# 3_F2838_GPIO.net
KiCad netlist of a schematic drawn in Altium Designer
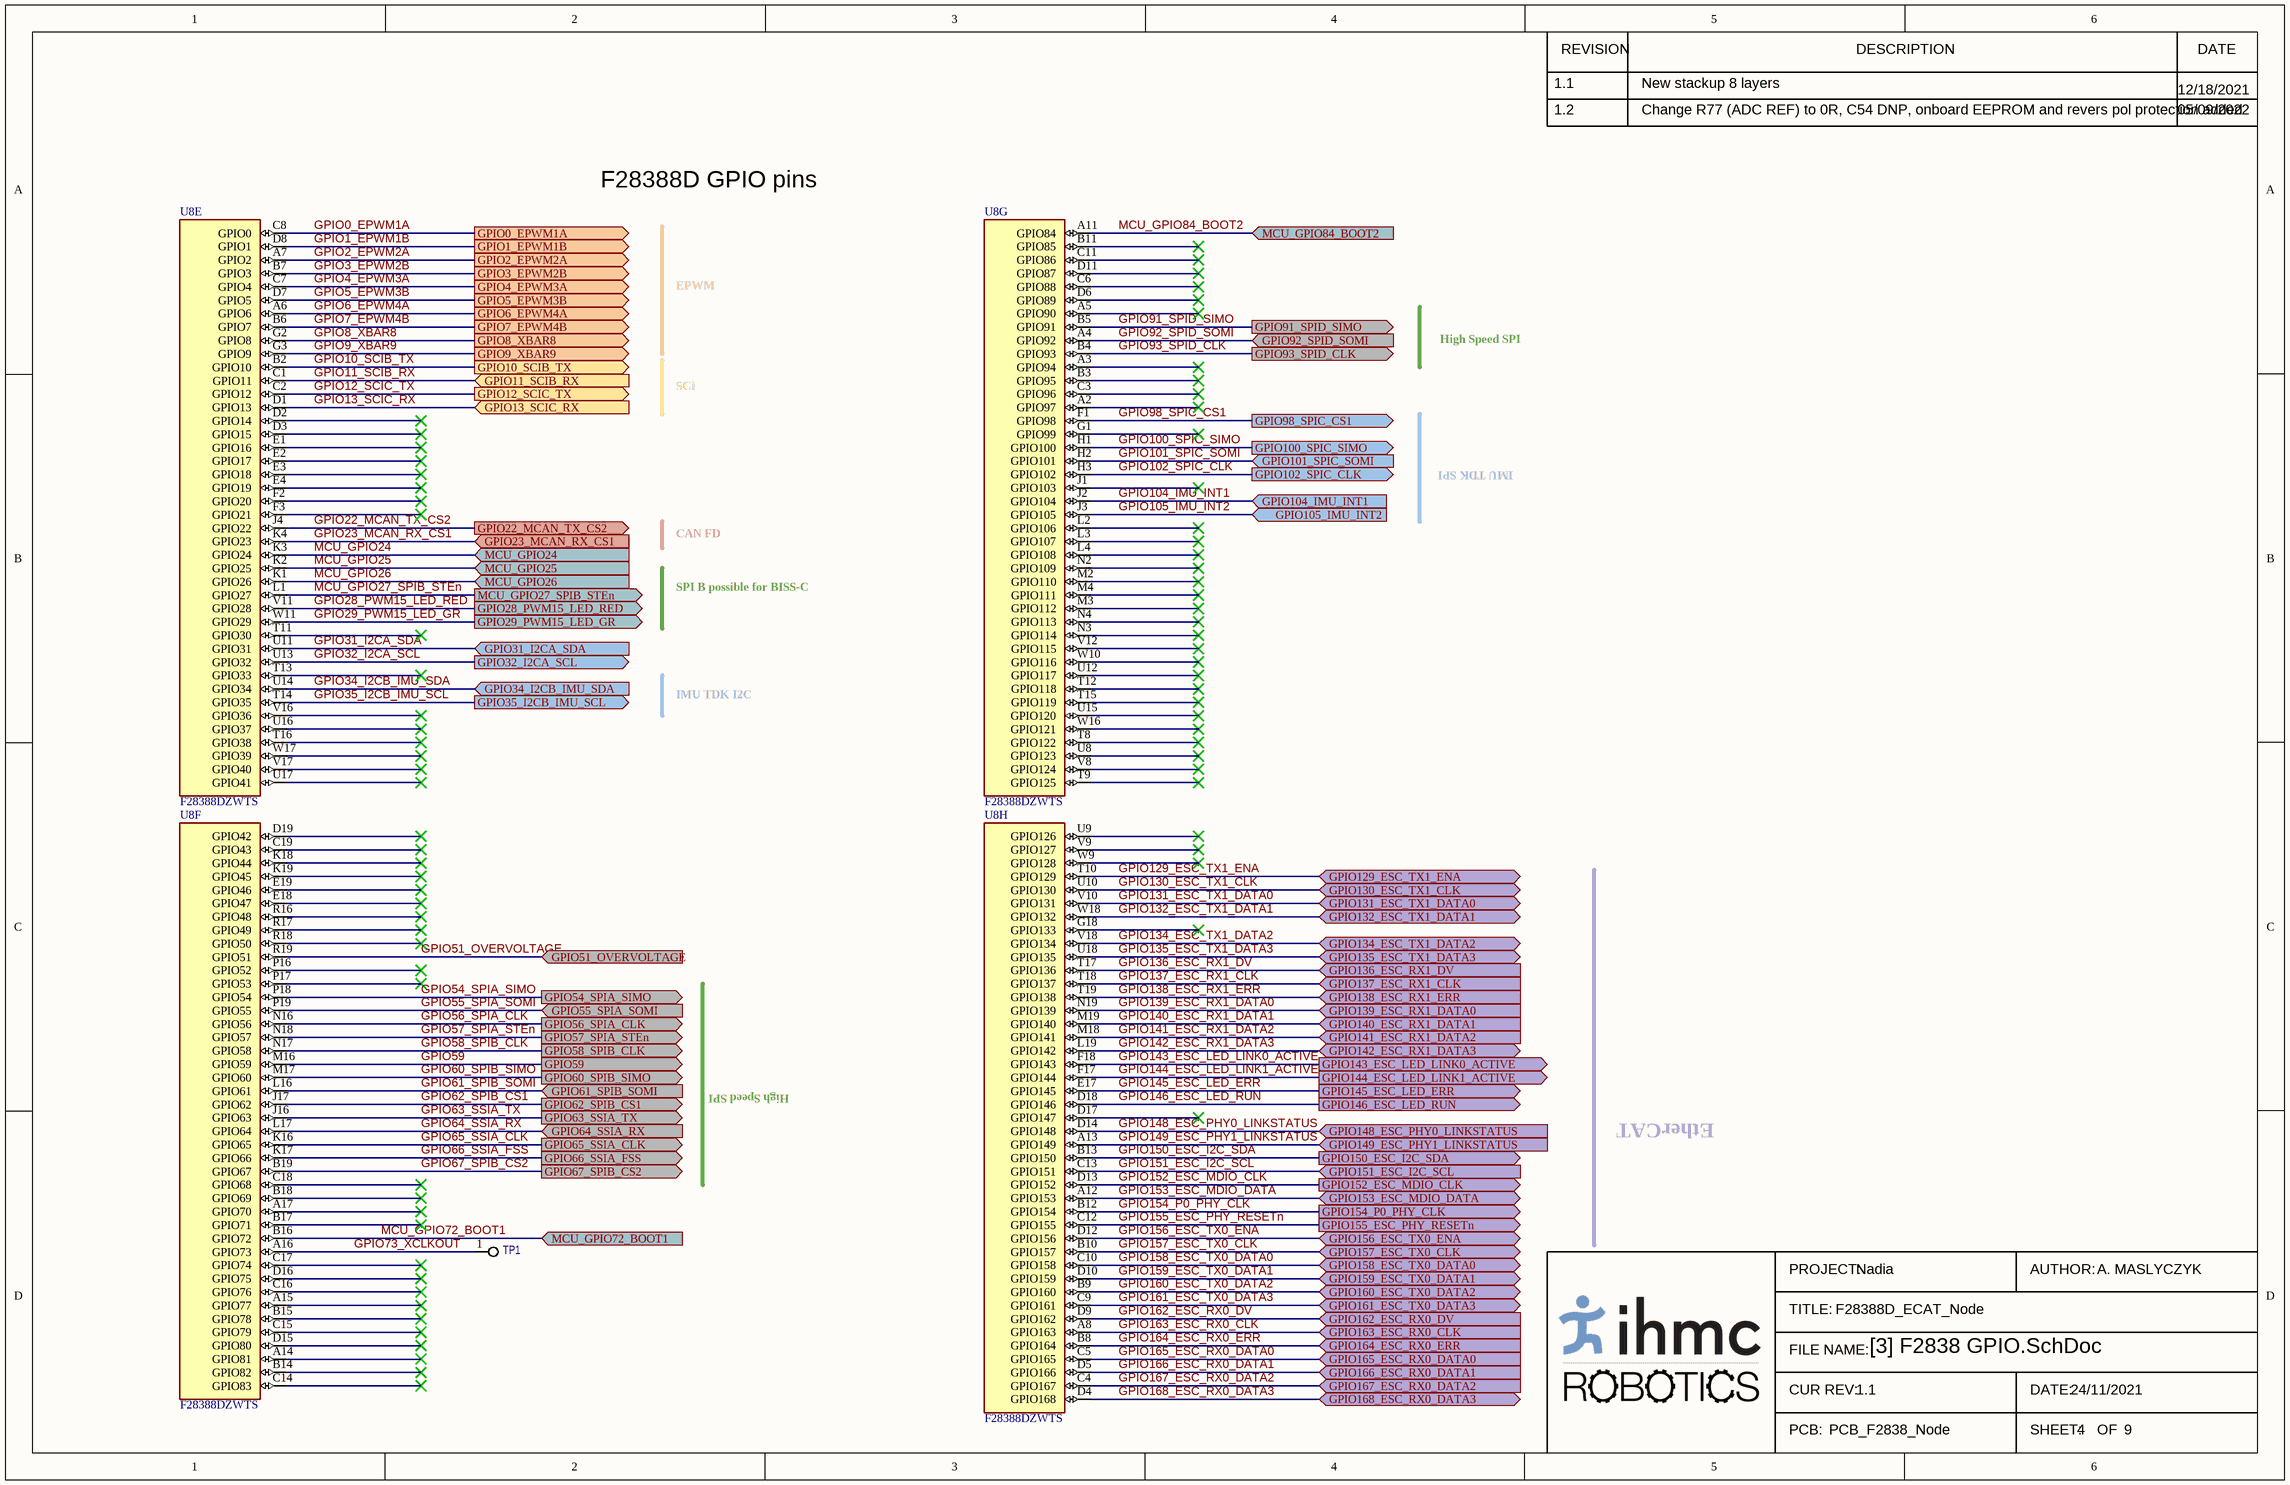
[diagram p0: [3] F2838 GPIO.SchDoc]

(export (version "E")
  (design (tool "Eeschema 10.0.6"))
  (components
    (comp (ref "TP1")
      (value "TP_SMD")
      (footprint "Pad_1mm")
      (description "Test point SMD")
      (libsource (lib "IHMC_Altium_Lib") (part "TP_SMD_1MM"))
    )
    (comp (ref "U8")
      (value "F28388DZWTS")
      (footprint "FP-ZWT0337A-IPC_B - ESNACK")
      (fields
        (field (name "MANUFACTURER") "Texas instruments")
        (field (name "OCTOPART") "https://octopart.com/f28388dzwts-texas+instruments-102550657")
      )
      (libsource (lib "IHMC_IC") (part "TMS320F28388D_32bit_uC"))
    )
  )
  (nets
    (net (code "1") (name "/GPIO0_EPWM1A") (class "Default")
      (node (ref "U8") (pin "C8") (pinfunction "GPIO0_C8") (pintype "bidirectional"))
    )
    (net (code "2") (name "/GPIO1_EPWM1B") (class "Default")
      (node (ref "U8") (pin "D8") (pinfunction "GPIO1_D8") (pintype "bidirectional"))
    )
    (net (code "3") (name "/GPIO2_EPWM2A") (class "Default")
      (node (ref "U8") (pin "A7") (pinfunction "GPIO2_A7") (pintype "bidirectional"))
    )
    (net (code "4") (name "/GPIO3_EPWM2B") (class "Default")
      (node (ref "U8") (pin "B7") (pinfunction "GPIO3_B7") (pintype "bidirectional"))
    )
    (net (code "5") (name "/GPIO4_EPWM3A") (class "Default")
      (node (ref "U8") (pin "C7") (pinfunction "GPIO4_C7") (pintype "bidirectional"))
    )
    (net (code "6") (name "/GPIO5_EPWM3B") (class "Default")
      (node (ref "U8") (pin "D7") (pinfunction "GPIO5_D7") (pintype "bidirectional"))
    )
    (net (code "7") (name "/GPIO6_EPWM4A") (class "Default")
      (node (ref "U8") (pin "A6") (pinfunction "GPIO6_A6") (pintype "bidirectional"))
    )
    (net (code "8") (name "/GPIO7_EPWM4B") (class "Default")
      (node (ref "U8") (pin "B6") (pinfunction "GPIO7_B6") (pintype "bidirectional"))
    )
    (net (code "9") (name "/GPIO8_XBAR8") (class "Default")
      (node (ref "U8") (pin "G2") (pinfunction "GPIO8_G2") (pintype "bidirectional"))
    )
    (net (code "10") (name "/GPIO9_XBAR9") (class "Default")
      (node (ref "U8") (pin "G3") (pinfunction "GPIO9_G3") (pintype "bidirectional"))
    )
    (net (code "11") (name "/GPIO10_SCIB_TX") (class "Default")
      (node (ref "U8") (pin "B2") (pinfunction "GPIO10_B2") (pintype "bidirectional"))
    )
    (net (code "12") (name "/GPIO11_SCIB_RX") (class "Default")
      (node (ref "U8") (pin "C1") (pinfunction "GPIO11_C1") (pintype "bidirectional"))
    )
    (net (code "13") (name "/GPIO12_SCIC_TX") (class "Default")
      (node (ref "U8") (pin "C2") (pinfunction "GPIO12_C2") (pintype "bidirectional"))
    )
    (net (code "14") (name "/GPIO13_SCIC_RX") (class "Default")
      (node (ref "U8") (pin "D1") (pinfunction "GPIO13_D1") (pintype "bidirectional"))
    )
    (net (code "15") (name "/GPIO22_MCAN_TX_CS2") (class "Default")
      (node (ref "U8") (pin "J4") (pinfunction "GPIO22_J4") (pintype "bidirectional"))
    )
    (net (code "16") (name "/GPIO23_MCAN_RX_CS1") (class "Default")
      (node (ref "U8") (pin "K4") (pinfunction "GPIO23_K4") (pintype "bidirectional"))
    )
    (net (code "17") (name "/GPIO28_PWM15_LED_RED") (class "Default")
      (node (ref "U8") (pin "V11") (pinfunction "GPIO28_V11") (pintype "bidirectional"))
    )
    (net (code "18") (name "/GPIO29_PWM15_LED_GR") (class "Default")
      (node (ref "U8") (pin "W11") (pinfunction "GPIO29_W11") (pintype "bidirectional"))
    )
    (net (code "19") (name "/GPIO31_I2CA_SDA") (class "Default")
      (node (ref "U8") (pin "U11") (pinfunction "GPIO31_U11") (pintype "bidirectional"))
    )
    (net (code "20") (name "/GPIO32_I2CA_SCL") (class "Default")
      (node (ref "U8") (pin "U13") (pinfunction "GPIO32_U13") (pintype "bidirectional"))
    )
    (net (code "21") (name "/GPIO34_I2CB_IMU_SDA") (class "Default")
      (node (ref "U8") (pin "U14") (pinfunction "GPIO34_U14") (pintype "bidirectional"))
    )
    (net (code "22") (name "/GPIO35_I2CB_IMU_SCL") (class "Default")
      (node (ref "U8") (pin "T14") (pinfunction "GPIO35_T14") (pintype "bidirectional"))
    )
    (net (code "23") (name "/GPIO51_OVERVOLTAGE") (class "Default")
      (node (ref "U8") (pin "R19") (pinfunction "GPIO51_R19") (pintype "bidirectional"))
    )
    (net (code "24") (name "/GPIO54_SPIA_SIMO") (class "Default")
      (node (ref "U8") (pin "P18") (pinfunction "GPIO54_P18") (pintype "bidirectional"))
    )
    (net (code "25") (name "/GPIO55_SPIA_SOMI") (class "Default")
      (node (ref "U8") (pin "P19") (pinfunction "GPIO55_P19") (pintype "bidirectional"))
    )
    (net (code "26") (name "/GPIO56_SPIA_CLK") (class "Default")
      (node (ref "U8") (pin "N16") (pinfunction "GPIO56_N16") (pintype "bidirectional"))
    )
    (net (code "27") (name "/GPIO57_SPIA_STEn") (class "Default")
      (node (ref "U8") (pin "N18") (pinfunction "GPIO57_N18") (pintype "bidirectional"))
    )
    (net (code "28") (name "/GPIO58_SPIB_CLK") (class "Default")
      (node (ref "U8") (pin "N17") (pinfunction "GPIO58_N17") (pintype "bidirectional"))
    )
    (net (code "29") (name "/GPIO59") (class "Default")
      (node (ref "U8") (pin "M16") (pinfunction "GPIO59_M16") (pintype "bidirectional"))
    )
    (net (code "30") (name "/GPIO60_SPIB_SIMO") (class "Default")
      (node (ref "U8") (pin "M17") (pinfunction "GPIO60_M17") (pintype "bidirectional"))
    )
    (net (code "31") (name "/GPIO61_SPIB_SOMI") (class "Default")
      (node (ref "U8") (pin "L16") (pinfunction "GPIO61_L16") (pintype "bidirectional"))
    )
    (net (code "32") (name "/GPIO62_SPIB_CS1") (class "Default")
      (node (ref "U8") (pin "J17") (pinfunction "GPIO62_J17") (pintype "bidirectional"))
    )
    (net (code "33") (name "/GPIO63_SSIA_TX") (class "Default")
      (node (ref "U8") (pin "J16") (pinfunction "GPIO63_J16") (pintype "bidirectional"))
    )
    (net (code "34") (name "/GPIO64_SSIA_RX") (class "Default")
      (node (ref "U8") (pin "L17") (pinfunction "GPIO64_L17") (pintype "bidirectional"))
    )
    (net (code "35") (name "/GPIO65_SSIA_CLK") (class "Default")
      (node (ref "U8") (pin "K16") (pinfunction "GPIO65_K16") (pintype "bidirectional"))
    )
    (net (code "36") (name "/GPIO66_SSIA_FSS") (class "Default")
      (node (ref "U8") (pin "K17") (pinfunction "GPIO66_K17") (pintype "bidirectional"))
    )
    (net (code "37") (name "/GPIO67_SPIB_CS2") (class "Default")
      (node (ref "U8") (pin "B19") (pinfunction "GPIO67_B19") (pintype "bidirectional"))
    )
    (net (code "38") (name "/GPIO73_XCLKOUT") (class "Default")
      (node (ref "TP1") (pin "1") (pinfunction "IN_1") (pintype "passive"))
      (node (ref "U8") (pin "A16") (pinfunction "GPIO73_A16") (pintype "bidirectional"))
    )
    (net (code "39") (name "/GPIO91_SPID_SIMO") (class "Default")
      (node (ref "U8") (pin "B5") (pinfunction "GPIO91_B5") (pintype "bidirectional"))
    )
    (net (code "40") (name "/GPIO92_SPID_SOMI") (class "Default")
      (node (ref "U8") (pin "A4") (pinfunction "GPIO92_A4") (pintype "bidirectional"))
    )
    (net (code "41") (name "/GPIO93_SPID_CLK") (class "Default")
      (node (ref "U8") (pin "B4") (pinfunction "GPIO93_B4") (pintype "bidirectional"))
    )
    (net (code "42") (name "/GPIO98_SPIC_CS1") (class "Default")
      (node (ref "U8") (pin "F1") (pinfunction "GPIO98_F1") (pintype "bidirectional"))
    )
    (net (code "43") (name "/GPIO100_SPIC_SIMO") (class "Default")
      (node (ref "U8") (pin "H1") (pinfunction "GPIO100_H1") (pintype "bidirectional"))
    )
    (net (code "44") (name "/GPIO101_SPIC_SOMI") (class "Default")
      (node (ref "U8") (pin "H2") (pinfunction "GPIO101_H2") (pintype "bidirectional"))
    )
    (net (code "45") (name "/GPIO102_SPIC_CLK") (class "Default")
      (node (ref "U8") (pin "H3") (pinfunction "GPIO102_H3") (pintype "bidirectional"))
    )
    (net (code "46") (name "/GPIO104_IMU_INT1") (class "Default")
      (node (ref "U8") (pin "J2") (pinfunction "GPIO104_J2") (pintype "bidirectional"))
    )
    (net (code "47") (name "/GPIO105_IMU_INT2") (class "Default")
      (node (ref "U8") (pin "J3") (pinfunction "GPIO105_J3") (pintype "bidirectional"))
    )
    (net (code "48") (name "/GPIO129_ESC_TX1_ENA") (class "Default")
      (node (ref "U8") (pin "T10") (pinfunction "GPIO129_T10") (pintype "bidirectional"))
    )
    (net (code "49") (name "/GPIO130_ESC_TX1_CLK") (class "Default")
      (node (ref "U8") (pin "U10") (pinfunction "GPIO130_U10") (pintype "bidirectional"))
    )
    (net (code "50") (name "/GPIO131_ESC_TX1_DATA0") (class "Default")
      (node (ref "U8") (pin "V10") (pinfunction "GPIO131_V10") (pintype "bidirectional"))
    )
    (net (code "51") (name "/GPIO132_ESC_TX1_DATA1") (class "Default")
      (node (ref "U8") (pin "W18") (pinfunction "GPIO132_W18") (pintype "bidirectional"))
    )
    (net (code "52") (name "/GPIO134_ESC_TX1_DATA2") (class "Default")
      (node (ref "U8") (pin "V18") (pinfunction "GPIO134_V18") (pintype "bidirectional"))
    )
    (net (code "53") (name "/GPIO135_ESC_TX1_DATA3") (class "Default")
      (node (ref "U8") (pin "U18") (pinfunction "GPIO135_U18") (pintype "bidirectional"))
    )
    (net (code "54") (name "/GPIO136_ESC_RX1_DV") (class "Default")
      (node (ref "U8") (pin "T17") (pinfunction "GPIO136_T17") (pintype "bidirectional"))
    )
    (net (code "55") (name "/GPIO137_ESC_RX1_CLK") (class "Default")
      (node (ref "U8") (pin "T18") (pinfunction "GPIO137_T18") (pintype "bidirectional"))
    )
    (net (code "56") (name "/GPIO138_ESC_RX1_ERR") (class "Default")
      (node (ref "U8") (pin "T19") (pinfunction "GPIO138_T19") (pintype "bidirectional"))
    )
    (net (code "57") (name "/GPIO139_ESC_RX1_DATA0") (class "Default")
      (node (ref "U8") (pin "N19") (pinfunction "GPIO139_N19") (pintype "bidirectional"))
    )
    (net (code "58") (name "/GPIO140_ESC_RX1_DATA1") (class "Default")
      (node (ref "U8") (pin "M19") (pinfunction "GPIO140_M19") (pintype "bidirectional"))
    )
    (net (code "59") (name "/GPIO141_ESC_RX1_DATA2") (class "Default")
      (node (ref "U8") (pin "M18") (pinfunction "GPIO141_M18") (pintype "bidirectional"))
    )
    (net (code "60") (name "/GPIO142_ESC_RX1_DATA3") (class "Default")
      (node (ref "U8") (pin "L19") (pinfunction "GPIO142_L19") (pintype "bidirectional"))
    )
    (net (code "61") (name "/GPIO143_ESC_LED_LINK0_ACTIVE") (class "Default")
      (node (ref "U8") (pin "F18") (pinfunction "GPIO143_F18") (pintype "bidirectional"))
    )
    (net (code "62") (name "/GPIO144_ESC_LED_LINK1_ACTIVE") (class "Default")
      (node (ref "U8") (pin "F17") (pinfunction "GPIO144_F17") (pintype "bidirectional"))
    )
    (net (code "63") (name "/GPIO145_ESC_LED_ERR") (class "Default")
      (node (ref "U8") (pin "E17") (pinfunction "GPIO145_E17") (pintype "bidirectional"))
    )
    (net (code "64") (name "/GPIO146_ESC_LED_RUN") (class "Default")
      (node (ref "U8") (pin "D18") (pinfunction "GPIO146_D18") (pintype "bidirectional"))
    )
    (net (code "65") (name "/GPIO148_ESC_PHY0_LINKSTATUS") (class "Default")
      (node (ref "U8") (pin "D14") (pinfunction "GPIO148_D14") (pintype "bidirectional"))
    )
    (net (code "66") (name "/GPIO149_ESC_PHY1_LINKSTATUS") (class "Default")
      (node (ref "U8") (pin "A13") (pinfunction "GPIO149_A13") (pintype "bidirectional"))
    )
    (net (code "67") (name "/GPIO150_ESC_I2C_SDA") (class "Default")
      (node (ref "U8") (pin "B13") (pinfunction "GPIO150_B13") (pintype "bidirectional"))
    )
    (net (code "68") (name "/GPIO151_ESC_I2C_SCL") (class "Default")
      (node (ref "U8") (pin "C13") (pinfunction "GPIO151_C13") (pintype "bidirectional"))
    )
    (net (code "69") (name "/GPIO152_ESC_MDIO_CLK") (class "Default")
      (node (ref "U8") (pin "D13") (pinfunction "GPIO152_D13") (pintype "bidirectional"))
    )
    (net (code "70") (name "/GPIO153_ESC_MDIO_DATA") (class "Default")
      (node (ref "U8") (pin "A12") (pinfunction "GPIO153_A12") (pintype "bidirectional"))
    )
    (net (code "71") (name "/GPIO154_P0_PHY_CLK") (class "Default")
      (node (ref "U8") (pin "B12") (pinfunction "GPIO154_B12") (pintype "bidirectional"))
    )
    (net (code "72") (name "/GPIO155_ESC_PHY_RESETn") (class "Default")
      (node (ref "U8") (pin "C12") (pinfunction "GPIO155_C12") (pintype "bidirectional"))
    )
    (net (code "73") (name "/GPIO156_ESC_TX0_ENA") (class "Default")
      (node (ref "U8") (pin "D12") (pinfunction "GPIO156_D12") (pintype "bidirectional"))
    )
    (net (code "74") (name "/GPIO157_ESC_TX0_CLK") (class "Default")
      (node (ref "U8") (pin "B10") (pinfunction "GPIO157_B10") (pintype "bidirectional"))
    )
    (net (code "75") (name "/GPIO158_ESC_TX0_DATA0") (class "Default")
      (node (ref "U8") (pin "C10") (pinfunction "GPIO158_C10") (pintype "bidirectional"))
    )
    (net (code "76") (name "/GPIO159_ESC_TX0_DATA1") (class "Default")
      (node (ref "U8") (pin "D10") (pinfunction "GPIO159_D10") (pintype "bidirectional"))
    )
    (net (code "77") (name "/GPIO160_ESC_TX0_DATA2") (class "Default")
      (node (ref "U8") (pin "B9") (pinfunction "GPIO160_B9") (pintype "bidirectional"))
    )
    (net (code "78") (name "/GPIO161_ESC_TX0_DATA3") (class "Default")
      (node (ref "U8") (pin "C9") (pinfunction "GPIO161_C9") (pintype "bidirectional"))
    )
    (net (code "79") (name "/GPIO162_ESC_RX0_DV") (class "Default")
      (node (ref "U8") (pin "D9") (pinfunction "GPIO162_D9") (pintype "bidirectional"))
    )
    (net (code "80") (name "/GPIO163_ESC_RX0_CLK") (class "Default")
      (node (ref "U8") (pin "A8") (pinfunction "GPIO163_A8") (pintype "bidirectional"))
    )
    (net (code "81") (name "/GPIO164_ESC_RX0_ERR") (class "Default")
      (node (ref "U8") (pin "B8") (pinfunction "GPIO164_B8") (pintype "bidirectional"))
    )
    (net (code "82") (name "/GPIO165_ESC_RX0_DATA0") (class "Default")
      (node (ref "U8") (pin "C5") (pinfunction "GPIO165_C5") (pintype "bidirectional"))
    )
    (net (code "83") (name "/GPIO166_ESC_RX0_DATA1") (class "Default")
      (node (ref "U8") (pin "D5") (pinfunction "GPIO166_D5") (pintype "bidirectional"))
    )
    (net (code "84") (name "/GPIO167_ESC_RX0_DATA2") (class "Default")
      (node (ref "U8") (pin "C4") (pinfunction "GPIO167_C4") (pintype "bidirectional"))
    )
    (net (code "85") (name "/GPIO168_ESC_RX0_DATA3") (class "Default")
      (node (ref "U8") (pin "D4") (pinfunction "GPIO168_D4") (pintype "bidirectional"))
    )
    (net (code "86") (name "/MCU_GPIO24") (class "Default")
      (node (ref "U8") (pin "K3") (pinfunction "GPIO24_K3") (pintype "bidirectional"))
    )
    (net (code "87") (name "/MCU_GPIO25") (class "Default")
      (node (ref "U8") (pin "K2") (pinfunction "GPIO25_K2") (pintype "bidirectional"))
    )
    (net (code "88") (name "/MCU_GPIO26") (class "Default")
      (node (ref "U8") (pin "K1") (pinfunction "GPIO26_K1") (pintype "bidirectional"))
    )
    (net (code "89") (name "/MCU_GPIO27_SPIB_STEn") (class "Default")
      (node (ref "U8") (pin "L1") (pinfunction "GPIO27_L1") (pintype "bidirectional"))
    )
    (net (code "90") (name "/MCU_GPIO72_BOOT1") (class "Default")
      (node (ref "U8") (pin "B16") (pinfunction "GPIO72_B16") (pintype "bidirectional"))
    )
    (net (code "91") (name "/MCU_GPIO84_BOOT2") (class "Default")
      (node (ref "U8") (pin "A11") (pinfunction "GPIO84_A11") (pintype "bidirectional"))
    )
    (net (code "92") (name "unconnected-(U8E-GPIO14-PadD2)") (class "Default")
      (node (ref "U8") (pin "D2") (pinfunction "GPIO14_D2") (pintype "bidirectional+no_connect"))
    )
    (net (code "93") (name "unconnected-(U8E-GPIO15-PadD3)") (class "Default")
      (node (ref "U8") (pin "D3") (pinfunction "GPIO15_D3") (pintype "bidirectional+no_connect"))
    )
    (net (code "94") (name "unconnected-(U8E-GPIO16-PadE1)") (class "Default")
      (node (ref "U8") (pin "E1") (pinfunction "GPIO16_E1") (pintype "bidirectional+no_connect"))
    )
    (net (code "95") (name "unconnected-(U8E-GPIO17-PadE2)") (class "Default")
      (node (ref "U8") (pin "E2") (pinfunction "GPIO17_E2") (pintype "bidirectional+no_connect"))
    )
    (net (code "96") (name "unconnected-(U8E-GPIO18-PadE3)") (class "Default")
      (node (ref "U8") (pin "E3") (pinfunction "GPIO18_E3") (pintype "bidirectional+no_connect"))
    )
    (net (code "97") (name "unconnected-(U8E-GPIO19-PadE4)") (class "Default")
      (node (ref "U8") (pin "E4") (pinfunction "GPIO19_E4") (pintype "bidirectional+no_connect"))
    )
    (net (code "98") (name "unconnected-(U8E-GPIO20-PadF2)") (class "Default")
      (node (ref "U8") (pin "F2") (pinfunction "GPIO20_F2") (pintype "bidirectional+no_connect"))
    )
    (net (code "99") (name "unconnected-(U8E-GPIO21-PadF3)") (class "Default")
      (node (ref "U8") (pin "F3") (pinfunction "GPIO21_F3") (pintype "bidirectional+no_connect"))
    )
    (net (code "100") (name "unconnected-(U8E-GPIO30-PadT11)") (class "Default")
      (node (ref "U8") (pin "T11") (pinfunction "GPIO30_T11") (pintype "bidirectional+no_connect"))
    )
    (net (code "101") (name "unconnected-(U8E-GPIO33-PadT13)") (class "Default")
      (node (ref "U8") (pin "T13") (pinfunction "GPIO33_T13") (pintype "bidirectional+no_connect"))
    )
    (net (code "102") (name "unconnected-(U8E-GPIO36-PadV16)") (class "Default")
      (node (ref "U8") (pin "V16") (pinfunction "GPIO36_V16") (pintype "bidirectional+no_connect"))
    )
    (net (code "103") (name "unconnected-(U8E-GPIO37-PadU16)") (class "Default")
      (node (ref "U8") (pin "U16") (pinfunction "GPIO37_U16") (pintype "bidirectional+no_connect"))
    )
    (net (code "104") (name "unconnected-(U8E-GPIO38-PadT16)") (class "Default")
      (node (ref "U8") (pin "T16") (pinfunction "GPIO38_T16") (pintype "bidirectional+no_connect"))
    )
    (net (code "105") (name "unconnected-(U8E-GPIO39-PadW17)") (class "Default")
      (node (ref "U8") (pin "W17") (pinfunction "GPIO39_W17") (pintype "bidirectional+no_connect"))
    )
    (net (code "106") (name "unconnected-(U8E-GPIO40-PadV17)") (class "Default")
      (node (ref "U8") (pin "V17") (pinfunction "GPIO40_V17") (pintype "bidirectional+no_connect"))
    )
    (net (code "107") (name "unconnected-(U8E-GPIO41-PadU17)") (class "Default")
      (node (ref "U8") (pin "U17") (pinfunction "GPIO41_U17") (pintype "bidirectional+no_connect"))
    )
    (net (code "108") (name "unconnected-(U8F-GPIO42-PadD19)") (class "Default")
      (node (ref "U8") (pin "D19") (pinfunction "GPIO42_D19") (pintype "bidirectional+no_connect"))
    )
    (net (code "109") (name "unconnected-(U8F-GPIO43-PadC19)") (class "Default")
      (node (ref "U8") (pin "C19") (pinfunction "GPIO43_C19") (pintype "bidirectional+no_connect"))
    )
    (net (code "110") (name "unconnected-(U8F-GPIO44-PadK18)") (class "Default")
      (node (ref "U8") (pin "K18") (pinfunction "GPIO44_K18") (pintype "bidirectional+no_connect"))
    )
    (net (code "111") (name "unconnected-(U8F-GPIO45-PadK19)") (class "Default")
      (node (ref "U8") (pin "K19") (pinfunction "GPIO45_K19") (pintype "bidirectional+no_connect"))
    )
    (net (code "112") (name "unconnected-(U8F-GPIO46-PadE19)") (class "Default")
      (node (ref "U8") (pin "E19") (pinfunction "GPIO46_E19") (pintype "bidirectional+no_connect"))
    )
    (net (code "113") (name "unconnected-(U8F-GPIO47-PadE18)") (class "Default")
      (node (ref "U8") (pin "E18") (pinfunction "GPIO47_E18") (pintype "bidirectional+no_connect"))
    )
    (net (code "114") (name "unconnected-(U8F-GPIO48-PadR16)") (class "Default")
      (node (ref "U8") (pin "R16") (pinfunction "GPIO48_R16") (pintype "bidirectional+no_connect"))
    )
    (net (code "115") (name "unconnected-(U8F-GPIO49-PadR17)") (class "Default")
      (node (ref "U8") (pin "R17") (pinfunction "GPIO49_R17") (pintype "bidirectional+no_connect"))
    )
    (net (code "116") (name "unconnected-(U8F-GPIO50-PadR18)") (class "Default")
      (node (ref "U8") (pin "R18") (pinfunction "GPIO50_R18") (pintype "bidirectional+no_connect"))
    )
    (net (code "117") (name "unconnected-(U8F-GPIO52-PadP16)") (class "Default")
      (node (ref "U8") (pin "P16") (pinfunction "GPIO52_P16") (pintype "bidirectional+no_connect"))
    )
    (net (code "118") (name "unconnected-(U8F-GPIO53-PadP17)") (class "Default")
      (node (ref "U8") (pin "P17") (pinfunction "GPIO53_P17") (pintype "bidirectional+no_connect"))
    )
    (net (code "119") (name "unconnected-(U8F-GPIO68-PadC18)") (class "Default")
      (node (ref "U8") (pin "C18") (pinfunction "GPIO68_C18") (pintype "bidirectional+no_connect"))
    )
    (net (code "120") (name "unconnected-(U8F-GPIO69-PadB18)") (class "Default")
      (node (ref "U8") (pin "B18") (pinfunction "GPIO69_B18") (pintype "bidirectional+no_connect"))
    )
    (net (code "121") (name "unconnected-(U8F-GPIO70-PadA17)") (class "Default")
      (node (ref "U8") (pin "A17") (pinfunction "GPIO70_A17") (pintype "bidirectional+no_connect"))
    )
    (net (code "122") (name "unconnected-(U8F-GPIO71-PadB17)") (class "Default")
      (node (ref "U8") (pin "B17") (pinfunction "GPIO71_B17") (pintype "bidirectional+no_connect"))
    )
    (net (code "123") (name "unconnected-(U8F-GPIO74-PadC17)") (class "Default")
      (node (ref "U8") (pin "C17") (pinfunction "GPIO74_C17") (pintype "bidirectional+no_connect"))
    )
    (net (code "124") (name "unconnected-(U8F-GPIO75-PadD16)") (class "Default")
      (node (ref "U8") (pin "D16") (pinfunction "GPIO75_D16") (pintype "bidirectional+no_connect"))
    )
    (net (code "125") (name "unconnected-(U8F-GPIO76-PadC16)") (class "Default")
      (node (ref "U8") (pin "C16") (pinfunction "GPIO76_C16") (pintype "bidirectional+no_connect"))
    )
    (net (code "126") (name "unconnected-(U8F-GPIO77-PadA15)") (class "Default")
      (node (ref "U8") (pin "A15") (pinfunction "GPIO77_A15") (pintype "bidirectional+no_connect"))
    )
    (net (code "127") (name "unconnected-(U8F-GPIO78-PadB15)") (class "Default")
      (node (ref "U8") (pin "B15") (pinfunction "GPIO78_B15") (pintype "bidirectional+no_connect"))
    )
    (net (code "128") (name "unconnected-(U8F-GPIO79-PadC15)") (class "Default")
      (node (ref "U8") (pin "C15") (pinfunction "GPIO79_C15") (pintype "bidirectional+no_connect"))
    )
    (net (code "129") (name "unconnected-(U8F-GPIO80-PadD15)") (class "Default")
      (node (ref "U8") (pin "D15") (pinfunction "GPIO80_D15") (pintype "bidirectional+no_connect"))
    )
    (net (code "130") (name "unconnected-(U8F-GPIO81-PadA14)") (class "Default")
      (node (ref "U8") (pin "A14") (pinfunction "GPIO81_A14") (pintype "bidirectional+no_connect"))
    )
    (net (code "131") (name "unconnected-(U8F-GPIO82-PadB14)") (class "Default")
      (node (ref "U8") (pin "B14") (pinfunction "GPIO82_B14") (pintype "bidirectional+no_connect"))
    )
    (net (code "132") (name "unconnected-(U8F-GPIO83-PadC14)") (class "Default")
      (node (ref "U8") (pin "C14") (pinfunction "GPIO83_C14") (pintype "bidirectional+no_connect"))
    )
    (net (code "133") (name "unconnected-(U8G-GPIO85-PadB11)") (class "Default")
      (node (ref "U8") (pin "B11") (pinfunction "GPIO85_B11") (pintype "bidirectional+no_connect"))
    )
    (net (code "134") (name "unconnected-(U8G-GPIO86-PadC11)") (class "Default")
      (node (ref "U8") (pin "C11") (pinfunction "GPIO86_C11") (pintype "bidirectional+no_connect"))
    )
    (net (code "135") (name "unconnected-(U8G-GPIO87-PadD11)") (class "Default")
      (node (ref "U8") (pin "D11") (pinfunction "GPIO87_D11") (pintype "bidirectional+no_connect"))
    )
    (net (code "136") (name "unconnected-(U8G-GPIO88-PadC6)") (class "Default")
      (node (ref "U8") (pin "C6") (pinfunction "GPIO88_C6") (pintype "bidirectional+no_connect"))
    )
    (net (code "137") (name "unconnected-(U8G-GPIO89-PadD6)") (class "Default")
      (node (ref "U8") (pin "D6") (pinfunction "GPIO89_D6") (pintype "bidirectional+no_connect"))
    )
    (net (code "138") (name "unconnected-(U8G-GPIO90-PadA5)") (class "Default")
      (node (ref "U8") (pin "A5") (pinfunction "GPIO90_A5") (pintype "bidirectional+no_connect"))
    )
    (net (code "139") (name "unconnected-(U8G-GPIO94-PadA3)") (class "Default")
      (node (ref "U8") (pin "A3") (pinfunction "GPIO94_A3") (pintype "bidirectional+no_connect"))
    )
    (net (code "140") (name "unconnected-(U8G-GPIO95-PadB3)") (class "Default")
      (node (ref "U8") (pin "B3") (pinfunction "GPIO95_B3") (pintype "bidirectional+no_connect"))
    )
    (net (code "141") (name "unconnected-(U8G-GPIO96-PadC3)") (class "Default")
      (node (ref "U8") (pin "C3") (pinfunction "GPIO96_C3") (pintype "bidirectional+no_connect"))
    )
    (net (code "142") (name "unconnected-(U8G-GPIO97-PadA2)") (class "Default")
      (node (ref "U8") (pin "A2") (pinfunction "GPIO97_A2") (pintype "bidirectional+no_connect"))
    )
    (net (code "143") (name "unconnected-(U8G-GPIO99-PadG1)") (class "Default")
      (node (ref "U8") (pin "G1") (pinfunction "GPIO99_G1") (pintype "bidirectional+no_connect"))
    )
    (net (code "144") (name "unconnected-(U8G-GPIO103-PadJ1)") (class "Default")
      (node (ref "U8") (pin "J1") (pinfunction "GPIO103_J1") (pintype "bidirectional+no_connect"))
    )
    (net (code "145") (name "unconnected-(U8G-GPIO106-PadL2)") (class "Default")
      (node (ref "U8") (pin "L2") (pinfunction "GPIO106_L2") (pintype "bidirectional+no_connect"))
    )
    (net (code "146") (name "unconnected-(U8G-GPIO107-PadL3)") (class "Default")
      (node (ref "U8") (pin "L3") (pinfunction "GPIO107_L3") (pintype "bidirectional+no_connect"))
    )
    (net (code "147") (name "unconnected-(U8G-GPIO108-PadL4)") (class "Default")
      (node (ref "U8") (pin "L4") (pinfunction "GPIO108_L4") (pintype "bidirectional+no_connect"))
    )
    (net (code "148") (name "unconnected-(U8G-GPIO109-PadN2)") (class "Default")
      (node (ref "U8") (pin "N2") (pinfunction "GPIO109_N2") (pintype "bidirectional+no_connect"))
    )
    (net (code "149") (name "unconnected-(U8G-GPIO110-PadM2)") (class "Default")
      (node (ref "U8") (pin "M2") (pinfunction "GPIO110_M2") (pintype "bidirectional+no_connect"))
    )
    (net (code "150") (name "unconnected-(U8G-GPIO111-PadM4)") (class "Default")
      (node (ref "U8") (pin "M4") (pinfunction "GPIO111_M4") (pintype "bidirectional+no_connect"))
    )
    (net (code "151") (name "unconnected-(U8G-GPIO112-PadM3)") (class "Default")
      (node (ref "U8") (pin "M3") (pinfunction "GPIO112_M3") (pintype "bidirectional+no_connect"))
    )
    (net (code "152") (name "unconnected-(U8G-GPIO113-PadN4)") (class "Default")
      (node (ref "U8") (pin "N4") (pinfunction "GPIO113_N4") (pintype "bidirectional+no_connect"))
    )
    (net (code "153") (name "unconnected-(U8G-GPIO114-PadN3)") (class "Default")
      (node (ref "U8") (pin "N3") (pinfunction "GPIO114_N3") (pintype "bidirectional+no_connect"))
    )
    (net (code "154") (name "unconnected-(U8G-GPIO115-PadV12)") (class "Default")
      (node (ref "U8") (pin "V12") (pinfunction "GPIO115_V12") (pintype "bidirectional+no_connect"))
    )
    (net (code "155") (name "unconnected-(U8G-GPIO116-PadW10)") (class "Default")
      (node (ref "U8") (pin "W10") (pinfunction "GPIO116_W10") (pintype "bidirectional+no_connect"))
    )
    (net (code "156") (name "unconnected-(U8G-GPIO117-PadU12)") (class "Default")
      (node (ref "U8") (pin "U12") (pinfunction "GPIO117_U12") (pintype "bidirectional+no_connect"))
    )
    (net (code "157") (name "unconnected-(U8G-GPIO118-PadT12)") (class "Default")
      (node (ref "U8") (pin "T12") (pinfunction "GPIO118_T12") (pintype "bidirectional+no_connect"))
    )
    (net (code "158") (name "unconnected-(U8G-GPIO119-PadT15)") (class "Default")
      (node (ref "U8") (pin "T15") (pinfunction "GPIO119_T15") (pintype "bidirectional+no_connect"))
    )
    (net (code "159") (name "unconnected-(U8G-GPIO120-PadU15)") (class "Default")
      (node (ref "U8") (pin "U15") (pinfunction "GPIO120_U15") (pintype "bidirectional+no_connect"))
    )
    (net (code "160") (name "unconnected-(U8G-GPIO121-PadW16)") (class "Default")
      (node (ref "U8") (pin "W16") (pinfunction "GPIO121_W16") (pintype "bidirectional+no_connect"))
    )
    (net (code "161") (name "unconnected-(U8G-GPIO122-PadT8)") (class "Default")
      (node (ref "U8") (pin "T8") (pinfunction "GPIO122_T8") (pintype "bidirectional+no_connect"))
    )
    (net (code "162") (name "unconnected-(U8G-GPIO123-PadU8)") (class "Default")
      (node (ref "U8") (pin "U8") (pinfunction "GPIO123_U8") (pintype "bidirectional+no_connect"))
    )
    (net (code "163") (name "unconnected-(U8G-GPIO124-PadV8)") (class "Default")
      (node (ref "U8") (pin "V8") (pinfunction "GPIO124_V8") (pintype "bidirectional+no_connect"))
    )
    (net (code "164") (name "unconnected-(U8G-GPIO125-PadT9)") (class "Default")
      (node (ref "U8") (pin "T9") (pinfunction "GPIO125_T9") (pintype "bidirectional+no_connect"))
    )
    (net (code "165") (name "unconnected-(U8H-GPIO126-PadU9)") (class "Default")
      (node (ref "U8") (pin "U9") (pinfunction "GPIO126_U9") (pintype "bidirectional+no_connect"))
    )
    (net (code "166") (name "unconnected-(U8H-GPIO127-PadV9)") (class "Default")
      (node (ref "U8") (pin "V9") (pinfunction "GPIO127_V9") (pintype "bidirectional+no_connect"))
    )
    (net (code "167") (name "unconnected-(U8H-GPIO128-PadW9)") (class "Default")
      (node (ref "U8") (pin "W9") (pinfunction "GPIO128_W9") (pintype "bidirectional+no_connect"))
    )
    (net (code "168") (name "unconnected-(U8H-GPIO133-PadG18)") (class "Default")
      (node (ref "U8") (pin "G18") (pinfunction "GPIO133_G18") (pintype "bidirectional+no_connect"))
    )
    (net (code "169") (name "unconnected-(U8H-GPIO147-PadD17)") (class "Default")
      (node (ref "U8") (pin "D17") (pinfunction "GPIO147_D17") (pintype "bidirectional+no_connect"))
    )
  )
)
